# BACKPMAN21_PwrSw.net
KiCad netlist of a schematic drawn in Altium Designer
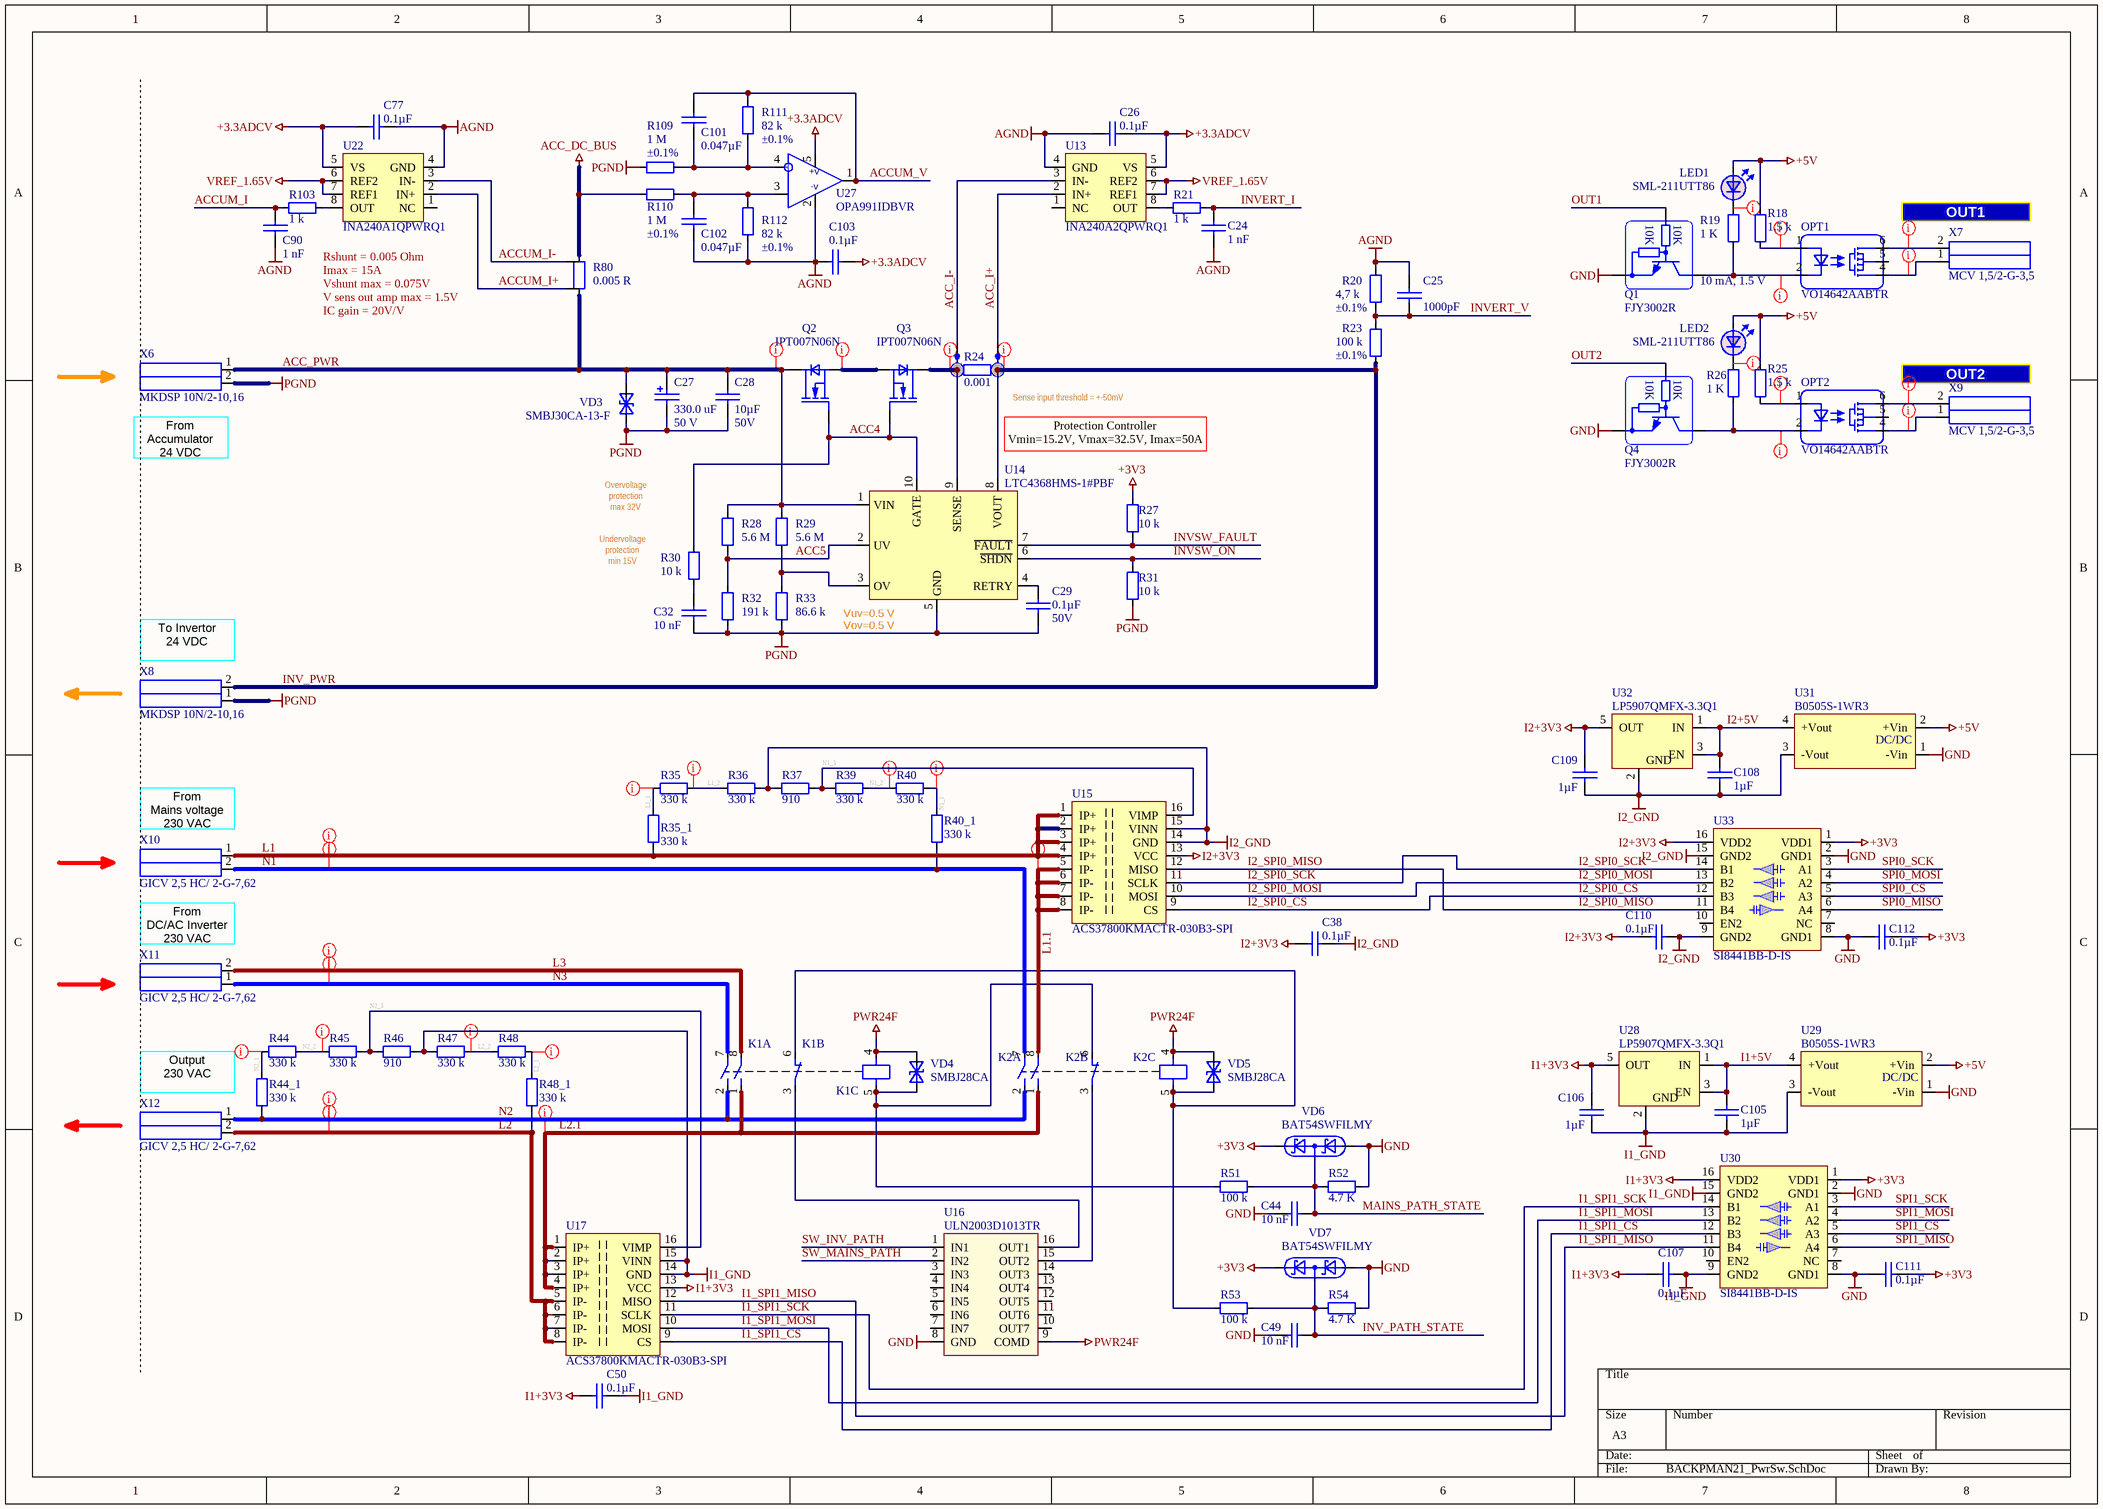
[diagram p0: BACKPMAN21_PwrSw.SchDoc]

(export (version "E")
  (design (tool "Eeschema 10.0.6"))
  (components
    (comp (ref "B1")
      (value "Net tie 0.3mm")
      (footprint "Net tee 0.3 mm")
      (libsource (lib "ea_Mechanical") (part "Net tie 0.3mm"))
    )
    (comp (ref "B2")
      (value "Net tie 0.3mm")
      (footprint "Net tee 0.3 mm")
      (libsource (lib "ea_Mechanical") (part "Net tie 0.3mm"))
    )
    (comp (ref "C24")
      (value "1 nF")
      (footprint "0603 CAP")
      (description "1000pF, ±5%, 50V, X7R, 0603 (1608 Metric), -55°C ~ 125°C, -, General Purpose")
      (fields (field (name "PART NUMBER") "CC0603JRX7R9BB102") (field (name "MANUFACTURER") "Yageo"))
      (libsource (lib "ea_PassivComps") (part "Capacitor"))
    )
    (comp (ref "C25")
      (value "1000pF")
      (footprint "0603 CAP")
      (description "1000pF, ±10%, 16V, X7R, 0603 (1608 Metric), -55°C ~ 125°C, -, General Purpose")
      (fields
        (field (name "PART NUMBER") "885012206034")
        (field (name "MANUFACTURER") "Wurth Electronics Inc.")
      )
      (libsource (lib "ea_PassivComps") (part "Capacitor"))
    )
    (comp (ref "C26")
      (value "0.1µF")
      (footprint "0603 CAP")
      (description "0.1µF, ±10%, 50V, X8L, 0603 (1608 Metric), -55°C ~ 150°C, -, Automotive")
      (fields
        (field (name "PART NUMBER") "GCM188L81H104KA57D")
        (field (name "MANUFACTURER") "Murata Electronics North America")
      )
      (libsource (lib "ea_PassivComps") (part "Capacitor"))
    )
    (comp (ref "C27")
      (value "330.0 uF")
      (footprint "UUD1V331MNL1GS")
      (description "330 uF, 50V, 120 mOhm @ 100kHz, 585 mA, 10x10, -50...+105 C")
      (fields
        (field (name "MANUFACTURER") "Panasonic Electronic Components")
        (field (name "VOLTAGE") "50 V")
        (field (name "TOLERANCE") "±20%")
      )
      (libsource (lib "ea_Capacitors") (part "EEE-FT1H331GP"))
    )
    (comp (ref "C28")
      (value "10µF")
      (footprint "1210 CAP")
      (description "10µF, ±10%, 50V, X7S, 1210 (3225 Metric), -55°C ~ 125°C, Low ESL, General Purpose")
      (fields
        (field (name "VOLTAGE - RATED") "50V")
        (field (name "PART NUMBER") "C3225X7S1H106K250AB")
        (field (name "MANUFACTURER") "TDK Corporation")
      )
      (libsource (lib "ea_PassivComps") (part "Capacitor"))
    )
    (comp (ref "C29")
      (value "0.1µF")
      (footprint "0603 CAP")
      (description "0.1µF, ±10%, 50V, X8L, 0603 (1608 Metric), -55°C ~ 150°C, -, Automotive")
      (fields
        (field (name "VOLTAGE - RATED") "50V")
        (field (name "PART NUMBER") "GCM188L81H104KA57D")
        (field (name "MANUFACTURER") "Murata Electronics North America")
      )
      (libsource (lib "ea_PassivComps") (part "Capacitor"))
    )
    (comp (ref "C32")
      (value "10 nF")
      (footprint "1608[0603]")
      (description "10 nF, 50V, 10%, X7R, 0603 SMD MLC Capacitor")
      (fields (field (name "TOLERANCE") "±10%") (field (name "MANUFACTURER") "Murata Electronics"))
      (libsource (lib "ea_Capacitors") (part "CVNF010K0603"))
    )
    (comp (ref "C38")
      (value "0.1µF")
      (footprint "0603 CAP")
      (description "0.1µF, ±10%, 16V, X7R, 0603 (1608 Metric), -55°C ~ 125°C, -, General Purpose")
      (fields
        (field (name "PART NUMBER") "CL10B104KO8NNNC")
        (field (name "MANUFACTURER") "Samsung Electro-Mechanics")
      )
      (libsource (lib "ea_PassivComps") (part "Capacitor"))
    )
    (comp (ref "C44")
      (value "10 nF")
      (footprint "1608[0603]")
      (description "10 nF, 50V, 10%, X7R, 0603 SMD MLC Capacitor")
      (fields (field (name "TOLERANCE") "±10%") (field (name "MANUFACTURER") "Murata Electronics"))
      (libsource (lib "ea_Capacitors") (part "CVNF010K0603"))
    )
    (comp (ref "C49")
      (value "10 nF")
      (footprint "1608[0603]")
      (description "10 nF, 50V, 10%, X7R, 0603 SMD MLC Capacitor")
      (fields (field (name "TOLERANCE") "±10%") (field (name "MANUFACTURER") "Murata Electronics"))
      (libsource (lib "ea_Capacitors") (part "CVNF010K0603"))
    )
    (comp (ref "C50")
      (value "0.1µF")
      (footprint "0603 CAP")
      (description "0.1µF, ±10%, 16V, X7R, 0603 (1608 Metric), -55°C ~ 125°C, -, General Purpose")
      (fields
        (field (name "PART NUMBER") "CL10B104KO8NNNC")
        (field (name "MANUFACTURER") "Samsung Electro-Mechanics")
      )
      (libsource (lib "ea_PassivComps") (part "Capacitor"))
    )
    (comp (ref "C77")
      (value "0.1µF")
      (footprint "0603 CAP")
      (description "0.1µF, ±10%, 50V, X8L, 0603 (1608 Metric), -55°C ~ 150°C, -, Automotive")
      (fields
        (field (name "PART NUMBER") "GCM188L81H104KA57D")
        (field (name "MANUFACTURER") "Murata Electronics North America")
      )
      (libsource (lib "ea_PassivComps") (part "Capacitor"))
    )
    (comp (ref "C90")
      (value "1 nF")
      (footprint "0603 CAP")
      (description "1000pF, ±5%, 50V, X7R, 0603 (1608 Metric), -55°C ~ 125°C, -, General Purpose")
      (fields (field (name "PART NUMBER") "CC0603JRX7R9BB102") (field (name "MANUFACTURER") "Yageo"))
      (libsource (lib "ea_PassivComps") (part "Capacitor"))
    )
    (comp (ref "C101")
      (value "0.047µF")
      (footprint "0603 CAP")
      (description "0.047µF, ±5%, 50V, X7R, 0603 (1608 Metric), -55°C ~ 125°C, -, General Purpose")
      (fields (field (name "PART NUMBER") "CC0603JRX7R9BB473") (field (name "MANUFACTURER") "Yageo"))
      (libsource (lib "ea_PassivComps") (part "Capacitor"))
    )
    (comp (ref "C102")
      (value "0.047µF")
      (footprint "0603 CAP")
      (description "0.047µF, ±5%, 50V, X7R, 0603 (1608 Metric), -55°C ~ 125°C, -, General Purpose")
      (fields (field (name "PART NUMBER") "CC0603JRX7R9BB473") (field (name "MANUFACTURER") "Yageo"))
      (libsource (lib "ea_PassivComps") (part "Capacitor"))
    )
    (comp (ref "C103")
      (value "0.1µF")
      (footprint "0603 CAP")
      (description "0.1µF, ±10%, 50V, X8L, 0603 (1608 Metric), -55°C ~ 150°C, -, Automotive")
      (fields
        (field (name "PART NUMBER") "GCM188L81H104KA57D")
        (field (name "MANUFACTURER") "Murata Electronics North America")
      )
      (libsource (lib "ea_PassivComps") (part "Capacitor"))
    )
    (comp (ref "C105")
      (value "1µF")
      (footprint "0603 CAP")
      (description "1µF, ±10%, 16V, X7R, 0603 (1608 Metric), -55°C ~ 125°C, -, General Purpose")
      (fields
        (field (name "PART NUMBER") "CL10B105KO8NNNC")
        (field (name "MANUFACTURER") "Samsung Electro-Mechanics")
      )
      (libsource (lib "ea_PassivComps") (part "Capacitor"))
    )
    (comp (ref "C106")
      (value "1µF")
      (footprint "0603 CAP")
      (description "1µF, ±10%, 16V, X7R, 0603 (1608 Metric), -55°C ~ 125°C, -, General Purpose")
      (fields
        (field (name "PART NUMBER") "CL10B105KO8NNNC")
        (field (name "MANUFACTURER") "Samsung Electro-Mechanics")
      )
      (libsource (lib "ea_PassivComps") (part "Capacitor"))
    )
    (comp (ref "C107")
      (value "0.1µF")
      (footprint "0603 CAP")
      (description "0.1µF, ±10%, 16V, X7R, 0603 (1608 Metric), -55°C ~ 125°C, -, General Purpose")
      (fields
        (field (name "PART NUMBER") "CL10B104KO8NNNC")
        (field (name "MANUFACTURER") "Samsung Electro-Mechanics")
      )
      (libsource (lib "ea_PassivComps") (part "Capacitor"))
    )
    (comp (ref "C108")
      (value "1µF")
      (footprint "0603 CAP")
      (description "1µF, ±10%, 16V, X7R, 0603 (1608 Metric), -55°C ~ 125°C, -, General Purpose")
      (fields
        (field (name "PART NUMBER") "CL10B105KO8NNNC")
        (field (name "MANUFACTURER") "Samsung Electro-Mechanics")
      )
      (libsource (lib "ea_PassivComps") (part "Capacitor"))
    )
    (comp (ref "C109")
      (value "1µF")
      (footprint "0603 CAP")
      (description "1µF, ±10%, 16V, X7R, 0603 (1608 Metric), -55°C ~ 125°C, -, General Purpose")
      (fields
        (field (name "PART NUMBER") "CL10B105KO8NNNC")
        (field (name "MANUFACTURER") "Samsung Electro-Mechanics")
      )
      (libsource (lib "ea_PassivComps") (part "Capacitor"))
    )
    (comp (ref "C110")
      (value "0.1µF")
      (footprint "0603 CAP")
      (description "0.1µF, ±10%, 16V, X7R, 0603 (1608 Metric), -55°C ~ 125°C, -, General Purpose")
      (fields
        (field (name "PART NUMBER") "CL10B104KO8NNNC")
        (field (name "MANUFACTURER") "Samsung Electro-Mechanics")
      )
      (libsource (lib "ea_PassivComps") (part "Capacitor"))
    )
    (comp (ref "C111")
      (value "0.1µF")
      (footprint "0603 CAP")
      (description "0.1µF, ±10%, 16V, X7R, 0603 (1608 Metric), -55°C ~ 125°C, -, General Purpose")
      (fields
        (field (name "PART NUMBER") "CL10B104KO8NNNC")
        (field (name "MANUFACTURER") "Samsung Electro-Mechanics")
      )
      (libsource (lib "ea_PassivComps") (part "Capacitor"))
    )
    (comp (ref "C112")
      (value "0.1µF")
      (footprint "0603 CAP")
      (description "0.1µF, ±10%, 16V, X7R, 0603 (1608 Metric), -55°C ~ 125°C, -, General Purpose")
      (fields
        (field (name "PART NUMBER") "CL10B104KO8NNNC")
        (field (name "MANUFACTURER") "Samsung Electro-Mechanics")
      )
      (libsource (lib "ea_PassivComps") (part "Capacitor"))
    )
    (comp (ref "K1")
      (value "AHES4292")
      (footprint "AHES4292")
      (fields (field (name "PARTNUM") "255-5914-ND") (field (name "MANUFACTURER") "Panasonic Electric Works"))
      (libsource (lib "ea_Relay") (part "AHES4292"))
    )
    (comp (ref "K2")
      (value "AHES4292")
      (footprint "AHES4292")
      (fields (field (name "PARTNUM") "255-5914-ND") (field (name "MANUFACTURER") "Panasonic Electric Works"))
      (libsource (lib "ea_Relay") (part "AHES4292"))
    )
    (comp (ref "LED1")
      (value "SML-211UTT86")
      (footprint "0805 LED")
      (description "0805 red LED, hibright, 2 mA, 1.8V, 130°")
      (fields (field (name "MANUFACTURER") "Rohm") (field (name "PARTNUM") "511-1292-1-ND"))
      (libsource (lib "ea_Indicators") (part "SML-211UTT86"))
    )
    (comp (ref "LED2")
      (value "SML-211UTT86")
      (footprint "0805 LED")
      (description "0805 red LED, hibright, 2 mA, 1.8V, 130°")
      (fields (field (name "MANUFACTURER") "Rohm") (field (name "PARTNUM") "511-1292-1-ND"))
      (libsource (lib "ea_Indicators") (part "SML-211UTT86"))
    )
    (comp (ref "OPT1")
      (value "VO14642AABTR")
      (footprint "DIP-6 SMD")
      (description "Opto relay, SPST-NO, AC DC, 250 mOhm, 2A, 0-60V, 6-SMD, -55..50C")
      (fields
        (field (name "MANUFACTURER") "Vishay Semiconductor Opto Division")
        (field (name "PARTNUM") "VO14642AABCT-ND")
      )
      (libsource (lib "ea_Opto") (part "VO14642AABTR"))
    )
    (comp (ref "OPT2")
      (value "VO14642AABTR")
      (footprint "DIP-6 SMD")
      (description "Opto relay, SPST-NO, AC DC, 250 mOhm, 2A, 0-60V, 6-SMD, -55..50C")
      (fields
        (field (name "MANUFACTURER") "Vishay Semiconductor Opto Division")
        (field (name "PARTNUM") "VO14642AABCT-ND")
      )
      (libsource (lib "ea_Opto") (part "VO14642AABTR"))
    )
    (comp (ref "Q1")
      (value "FJY3002R")
      (footprint "SOT-523F")
      (description "NPN 50V 100MA SOT-523F")
      (fields
        (field (name "MANUFACTURER") "Fairchild Semiconductor")
        (field (name "PARTNUM") "FJY3002RCT-ND")
      )
      (libsource (lib "ea_Transistors") (part "FJY3002R"))
    )
    (comp (ref "Q2")
      (value "IPT007N06N")
      (footprint "PG-HSOF-8-1 (8-PowerSFN) Infineon")
      (description "MOSFET N CH 60V 300A, 0.75 mOhm @ 150A 10V, 287nC @ 10V, PG-HSOF-8-1, -55°C ~ 175°C")
      (fields
        (field (name "MANUFACTURER") "Infineon Technologies")
        (field (name "PARTNUM") "IPT007N06NATMA1CT-ND")
      )
      (libsource (lib "ea_MOSFET_&_drivers") (part "IPT007N06NATMA1"))
    )
    (comp (ref "Q3")
      (value "IPT007N06N")
      (footprint "PG-HSOF-8-1 (8-PowerSFN) Infineon")
      (description "MOSFET N CH 60V 300A, 0.75 mOhm @ 150A 10V, 287nC @ 10V, PG-HSOF-8-1, -55°C ~ 175°C")
      (fields
        (field (name "MANUFACTURER") "Infineon Technologies")
        (field (name "PARTNUM") "IPT007N06NATMA1CT-ND")
      )
      (libsource (lib "ea_MOSFET_&_drivers") (part "IPT007N06NATMA1"))
    )
    (comp (ref "Q4")
      (value "FJY3002R")
      (footprint "SOT-523F")
      (description "NPN 50V 100MA SOT-523F")
      (fields
        (field (name "MANUFACTURER") "Fairchild Semiconductor")
        (field (name "PARTNUM") "FJY3002RCT-ND")
      )
      (libsource (lib "ea_Transistors") (part "FJY3002R"))
    )
    (comp (ref "R18")
      (value "1.5 k")
      (footprint "0603")
      (fields
        (field (name "MANUFACTURER") "Stackpole Electronics Inc.")
        (field (name "TOLERANCE") "±1%")
        (field (name "VOLTAGE") "75V")
      )
      (libsource (lib "") (part "Resistor_2"))
    )
    (comp (ref "R19")
      (value "1 K")
      (footprint "0603")
      (description "1 K, 1%, 0603, SMD Resistor, Taped")
      (fields (field (name "MANUFACTURER") "Vishay") (field (name "TOLERANCE") "1%"))
      (libsource (lib "ea_Resistors_0603") (part "RL0603K001-1"))
    )
    (comp (ref "R20")
      (value "4,7 k")
      (footprint "0603")
      (fields
        (field (name "MANUFACTURER") "Panasonic Electronic Components")
        (field (name "TOLERANCE") "±0.1%")
        (field (name "VOLTAGE") "75V")
        (field (name "PARTNUM") "P4.7KDBCT-ND")
      )
      (libsource (lib "") (part "Resistor_3"))
    )
    (comp (ref "R21")
      (value "1 k")
      (footprint "0603")
      (fields
        (field (name "MANUFACTURER") "Stackpole Electronics Inc.")
        (field (name "TOLERANCE") "±1%")
        (field (name "VOLTAGE") "75V")
      )
      (libsource (lib "ea_PassivComps") (part "Resistor"))
    )
    (comp (ref "R23")
      (value "100 k")
      (footprint "1206")
      (fields
        (field (name "MANUFACTURER") "Panasonic Electronic Components")
        (field (name "TOLERANCE") "±0.1%")
        (field (name "VOLTAGE") "200V")
        (field (name "PARTNUM") "ERA-8APB104V")
      )
      (libsource (lib "") (part "Resistor_2"))
    )
    (comp (ref "R24")
      (value "0.001")
      (footprint "WSR52L000FEA")
      (description "Curr.sens.res. 0.001 OHM 5W 1% 4527 SMD")
      (fields (field (name "MANUFACTURER") "Vishay/Dale") (field (name "TOLERANCE") "1%"))
      (libsource (lib "ea_Resistors") (part "WSR51L000FEA"))
    )
    (comp (ref "R25")
      (value "1.5 k")
      (footprint "0603")
      (fields
        (field (name "MANUFACTURER") "Stackpole Electronics Inc.")
        (field (name "TOLERANCE") "±1%")
        (field (name "VOLTAGE") "75V")
      )
      (libsource (lib "") (part "Resistor_2"))
    )
    (comp (ref "R26")
      (value "1 K")
      (footprint "0603")
      (description "1 K, 1%, 0603, SMD Resistor, Taped")
      (fields (field (name "MANUFACTURER") "Vishay") (field (name "TOLERANCE") "1%"))
      (libsource (lib "ea_Resistors_0603") (part "RL0603K001-1"))
    )
    (comp (ref "R27")
      (value "10 k")
      (footprint "0603")
      (fields
        (field (name "MANUFACTURER") "Bourns Inc.")
        (field (name "TOLERANCE") "±1%")
        (field (name "VOLTAGE") "75V")
      )
      (libsource (lib "") (part "Resistor_1"))
    )
    (comp (ref "R28")
      (value "5.6 M")
      (footprint "0805")
      (fields
        (field (name "MANUFACTURER") "Vishay Dale")
        (field (name "TOLERANCE") "±1%")
        (field (name "VOLTAGE") "150V")
      )
      (libsource (lib "") (part "Resistor_1"))
    )
    (comp (ref "R29")
      (value "5.6 M")
      (footprint "0805")
      (fields
        (field (name "MANUFACTURER") "Vishay Dale")
        (field (name "TOLERANCE") "±1%")
        (field (name "VOLTAGE") "150V")
      )
      (libsource (lib "") (part "Resistor_1"))
    )
    (comp (ref "R30")
      (value "10 k")
      (footprint "0603")
      (fields
        (field (name "MANUFACTURER") "Bourns Inc.")
        (field (name "TOLERANCE") "±1%")
        (field (name "VOLTAGE") "75V")
      )
      (libsource (lib "") (part "Resistor_3"))
    )
    (comp (ref "R31")
      (value "10 k")
      (footprint "0603")
      (fields
        (field (name "MANUFACTURER") "Bourns Inc.")
        (field (name "TOLERANCE") "±1%")
        (field (name "VOLTAGE") "75V")
      )
      (libsource (lib "") (part "Resistor_1"))
    )
    (comp (ref "R32")
      (value "191 k")
      (footprint "0603")
      (fields
        (field (name "MANUFACTURER") "Stackpole Electronics Inc.")
        (field (name "TOLERANCE") "±1%")
        (field (name "VOLTAGE") "75V")
      )
      (libsource (lib "") (part "Resistor_1"))
    )
    (comp (ref "R33")
      (value "86.6 k")
      (footprint "0603")
      (fields
        (field (name "MANUFACTURER") "Stackpole Electronics Inc.")
        (field (name "TOLERANCE") "±1%")
        (field (name "VOLTAGE") "75V")
      )
      (libsource (lib "") (part "Resistor_1"))
    )
    (comp (ref "R35")
      (value "330 k")
      (footprint "1206")
      (fields
        (field (name "MANUFACTURER") "Stackpole Electronics Inc.")
        (field (name "TOLERANCE") "±1%")
        (field (name "VOLTAGE") "200V")
      )
      (libsource (lib "ea_PassivComps") (part "Resistor"))
    )
    (comp (ref "R35_1")
      (value "330 k")
      (footprint "1206")
      (fields
        (field (name "MANUFACTURER") "Stackpole Electronics Inc.")
        (field (name "TOLERANCE") "±1%")
        (field (name "VOLTAGE") "200V")
      )
      (libsource (lib "") (part "Resistor_1"))
    )
    (comp (ref "R36")
      (value "330 k")
      (footprint "1206")
      (fields
        (field (name "MANUFACTURER") "Stackpole Electronics Inc.")
        (field (name "TOLERANCE") "±1%")
        (field (name "VOLTAGE") "200V")
      )
      (libsource (lib "ea_PassivComps") (part "Resistor"))
    )
    (comp (ref "R37")
      (value "910")
      (footprint "0603")
      (fields
        (field (name "MANUFACTURER") "Stackpole Electronics Inc.")
        (field (name "TOLERANCE") "±1%")
        (field (name "VOLTAGE") "75V")
      )
      (libsource (lib "ea_PassivComps") (part "Resistor"))
    )
    (comp (ref "R39")
      (value "330 k")
      (footprint "1206")
      (fields
        (field (name "MANUFACTURER") "Stackpole Electronics Inc.")
        (field (name "TOLERANCE") "±1%")
        (field (name "VOLTAGE") "200V")
      )
      (libsource (lib "ea_PassivComps") (part "Resistor"))
    )
    (comp (ref "R40")
      (value "330 k")
      (footprint "1206")
      (fields
        (field (name "MANUFACTURER") "Stackpole Electronics Inc.")
        (field (name "TOLERANCE") "±1%")
        (field (name "VOLTAGE") "200V")
      )
      (libsource (lib "ea_PassivComps") (part "Resistor"))
    )
    (comp (ref "R40_1")
      (value "330 k")
      (footprint "1206")
      (fields
        (field (name "MANUFACTURER") "Stackpole Electronics Inc.")
        (field (name "TOLERANCE") "±1%")
        (field (name "VOLTAGE") "200V")
      )
      (libsource (lib "") (part "Resistor_1"))
    )
    (comp (ref "R44")
      (value "330 k")
      (footprint "1206")
      (fields
        (field (name "MANUFACTURER") "Stackpole Electronics Inc.")
        (field (name "TOLERANCE") "±1%")
        (field (name "VOLTAGE") "200V")
      )
      (libsource (lib "ea_PassivComps") (part "Resistor"))
    )
    (comp (ref "R44_1")
      (value "330 k")
      (footprint "1206")
      (fields
        (field (name "MANUFACTURER") "Stackpole Electronics Inc.")
        (field (name "TOLERANCE") "±1%")
        (field (name "VOLTAGE") "200V")
      )
      (libsource (lib "") (part "Resistor_1"))
    )
    (comp (ref "R45")
      (value "330 k")
      (footprint "1206")
      (fields
        (field (name "MANUFACTURER") "Stackpole Electronics Inc.")
        (field (name "TOLERANCE") "±1%")
        (field (name "VOLTAGE") "200V")
      )
      (libsource (lib "ea_PassivComps") (part "Resistor"))
    )
    (comp (ref "R46")
      (value "910")
      (footprint "0603")
      (fields
        (field (name "MANUFACTURER") "Stackpole Electronics Inc.")
        (field (name "TOLERANCE") "±1%")
        (field (name "VOLTAGE") "75V")
      )
      (libsource (lib "ea_PassivComps") (part "Resistor"))
    )
    (comp (ref "R47")
      (value "330 k")
      (footprint "1206")
      (fields
        (field (name "MANUFACTURER") "Stackpole Electronics Inc.")
        (field (name "TOLERANCE") "±1%")
        (field (name "VOLTAGE") "200V")
      )
      (libsource (lib "ea_PassivComps") (part "Resistor"))
    )
    (comp (ref "R48")
      (value "330 k")
      (footprint "1206")
      (fields
        (field (name "MANUFACTURER") "Stackpole Electronics Inc.")
        (field (name "TOLERANCE") "±1%")
        (field (name "VOLTAGE") "200V")
      )
      (libsource (lib "ea_PassivComps") (part "Resistor"))
    )
    (comp (ref "R48_1")
      (value "330 k")
      (footprint "1206")
      (fields
        (field (name "MANUFACTURER") "Stackpole Electronics Inc.")
        (field (name "TOLERANCE") "±1%")
        (field (name "VOLTAGE") "200V")
      )
      (libsource (lib "") (part "Resistor_1"))
    )
    (comp (ref "R51")
      (value "100 k")
      (footprint "1206")
      (fields
        (field (name "MANUFACTURER") "Stackpole Electronics Inc.")
        (field (name "TOLERANCE") "±1%")
        (field (name "VOLTAGE") "200V")
      )
      (libsource (lib "ea_PassivComps") (part "Resistor"))
    )
    (comp (ref "R52")
      (value "4.7 K")
      (footprint "0603")
      (description "4.7 K, 1%, 0603, SMD Resistor, Taped")
      (fields (field (name "MANUFACTURER") "Vishay Dale") (field (name "TOLERANCE") "1%"))
      (libsource (lib "ea_Resistors") (part "RL0603K004.7-1"))
    )
    (comp (ref "R53")
      (value "100 k")
      (footprint "1206")
      (fields
        (field (name "MANUFACTURER") "Stackpole Electronics Inc.")
        (field (name "TOLERANCE") "±1%")
        (field (name "VOLTAGE") "200V")
      )
      (libsource (lib "ea_PassivComps") (part "Resistor"))
    )
    (comp (ref "R54")
      (value "4.7 K")
      (footprint "0603")
      (description "4.7 K, 1%, 0603, SMD Resistor, Taped")
      (fields (field (name "MANUFACTURER") "Vishay Dale") (field (name "TOLERANCE") "1%"))
      (libsource (lib "ea_Resistors") (part "RL0603K004.7-1"))
    )
    (comp (ref "R80")
      (value "0.005 R")
      (footprint "FC4L110")
      (description "Curr.sens.res. 0.005 OHM 5W 1% , 4320 (50110 Metric)")
      (fields (field (name "MANUFACTURER") "Ohmite") (field (name "TOLERANCE") "1%"))
      (libsource (lib "ea_Resistors") (part "FC4L110R005FER"))
    )
    (comp (ref "R103")
      (value "1 k")
      (footprint "0603")
      (fields
        (field (name "MANUFACTURER") "Stackpole Electronics Inc.")
        (field (name "TOLERANCE") "±1%")
        (field (name "VOLTAGE") "75V")
      )
      (libsource (lib "") (part "Resistor_3"))
    )
    (comp (ref "R109")
      (value "1 M")
      (footprint "0603")
      (description "1 MOhms, ±0.1%, 0.1W, 1/10W, Thin Film, ±25ppm/°C, 0603 (1608 Metric), -55°C ~ 155°C, -")
      (fields
        (field (name "MANUFACTURER") "Yageo")
        (field (name "TOLERANCE") "±0.1%")
        (field (name "VOLTAGE") "75V")
      )
      (libsource (lib "ea_PassivComps") (part "Resistor"))
    )
    (comp (ref "R110")
      (value "1 M")
      (footprint "0603")
      (description "1 MOhms, ±0.1%, 0.1W, 1/10W, Thin Film, ±25ppm/°C, 0603 (1608 Metric), -55°C ~ 155°C, -")
      (fields
        (field (name "MANUFACTURER") "Yageo")
        (field (name "TOLERANCE") "±0.1%")
        (field (name "VOLTAGE") "75V")
      )
      (libsource (lib "ea_PassivComps") (part "Resistor"))
    )
    (comp (ref "R111")
      (value "82 k")
      (footprint "0603")
      (fields
        (field (name "MANUFACTURER") "Panasonic Electronic Components")
        (field (name "TOLERANCE") "±0.1%")
        (field (name "VOLTAGE") "75V")
        (field (name "PARTNUM") "P82KDBCT-ND")
      )
      (libsource (lib "") (part "Resistor_1"))
    )
    (comp (ref "R112")
      (value "82 k")
      (footprint "0603")
      (fields
        (field (name "MANUFACTURER") "Panasonic Electronic Components")
        (field (name "TOLERANCE") "±0.1%")
        (field (name "VOLTAGE") "75V")
        (field (name "PARTNUM") "P82KDBCT-ND")
      )
      (libsource (lib "") (part "Resistor_1"))
    )
    (comp (ref "U13")
      (value "INA240A2QPWRQ1")
      (footprint "TI TSSOP-8")
      (description "Current Sense Amplifier, 50V/V, 2V/us, 400KHz, -40°C ~ 125°C, 8-TSSOP")
      (fields (field (name "MANUFACTURER") "Texas Instruments") (field (name "PARTNUM") "296-50473-1-ND"))
      (libsource (lib "ea_IC_OPAmps_AnComparators") (part "INA240A2QPWRQ1"))
    )
    (comp (ref "U14")
      (value "LTC4368HMS-1#PBF")
      (footprint "10-Lead Plastic MSOP Linear")
      (fields (field (name "MANUFACTURER") "Analog Devices") (field (name "PARTNUM") "LTC4368HMS-1#PBF-ND"))
      (libsource (lib "ea_IC_drivers") (part "LTC4368HMS-1_PBF"))
    )
    (comp (ref "U15")
      (value "ACS37800KMACTR-030B3-SPI")
      (footprint "16-Pin SOICW")
      (fields
        (field (name "MANUFACTURER") "Allegro MicroSystems")
        (field (name "PARTNUM") "620-ACS37800KMACTR-030B3-SPICT-ND")
      )
      (libsource (lib "ea_IC_sensors") (part "ACS37800KMACTR-030B3-SPI"))
    )
    (comp (ref "U16")
      (value "ULN2003D1013TR")
      (footprint "SO-16")
      (description "TRANS 7 NPN DARL 50V 500MA 16SO")
      (fields (field (name "MANUFACTURER") "STMicroelectronics") (field (name "PARTNUM") "497-2345-1-ND"))
      (libsource (lib "ea_IC_registers_buffers") (part "ULN2003D1013TR"))
    )
    (comp (ref "U17")
      (value "ACS37800KMACTR-030B3-SPI")
      (footprint "16-Pin SOICW")
      (fields
        (field (name "MANUFACTURER") "Allegro MicroSystems")
        (field (name "PARTNUM") "620-ACS37800KMACTR-030B3-SPICT-ND")
      )
      (libsource (lib "ea_IC_sensors") (part "ACS37800KMACTR-030B3-SPI"))
    )
    (comp (ref "U22")
      (value "INA240A1QPWRQ1")
      (footprint "TI TSSOP-8")
      (description "Current Sense Amplifier, 20V/V, 2V/us, 400KHz, -40°C ~ 125°C, 8-TSSOP")
      (fields (field (name "MANUFACTURER") "Texas Instruments") (field (name "PARTNUM") "296-50472-1-ND"))
      (libsource (lib "ea_IC_OPAmps_AnComparators") (part "INA240A1QPWRQ1"))
    )
    (comp (ref "U27")
      (value "OPA991IDBVR")
      (footprint "SOT23-5")
      (description "OpAmp,  Rail-to-Rail,  4,5MHz, VSS 2.7V ~ 40V, Vofs125µV,  SOT-23-5, -40°C ~ 125°C")
      (fields
        (field (name "MANUFACTURER") "Texas Instruments")
        (field (name "PARTNUM") "296-OPA991IDBVRCT-ND")
      )
      (libsource (lib "ea_IC_OPAmps_AnComparators") (part "OPA991IDBVR"))
    )
    (comp (ref "U28")
      (value "LP5907QMFX-3.3Q1")
      (footprint "SOT23-5")
      (description "LDO 3.3 V, 250 mA, Vin < 5.5V, Iq < 12uA, -40..+125 C, SOT23-5")
      (fields (field (name "MANUFACTURER") "Texas Instruments") (field (name "PARTNUM") "296-40365-1-ND"))
      (libsource (lib "ea_IC_Power_Reg_Ref_Sw") (part "LP5907QMFX-3.3Q1"))
    )
    (comp (ref "U29")
      (value "B0505S-1WR3")
      (footprint "Recom 4-SIP module")
      (description "200mA, DC-DC Unregulated Single Output , 5V in, 5 V out,  -40°C ~ 105°C")
      (fields
        (field (name "MANUFACTURER") "Mornsun America, LLC")
        (field (name "PARTNUM") "2725-B0505S-1WR3-ND")
      )
      (libsource (lib "ea_PowerSources") (part "B0505S-1WR3"))
    )
    (comp (ref "U30")
      (value "SI8441BB-D-IS")
      (footprint "SO-G16/D10.4")
      (description "IC ISOLATOR 4CH 5.5V 16-SOIC")
      (fields
        (field (name "MANUFACTURER") "Silicon Laboratories Inc")
        (field (name "PARTNUM") "336-1762-5-ND")
      )
      (libsource (lib "ea_IC_Isolated_Interfaces") (part "SI8441BB-D-IS"))
    )
    (comp (ref "U31")
      (value "B0505S-1WR3")
      (footprint "Recom 4-SIP module")
      (description "200mA, DC-DC Unregulated Single Output , 5V in, 5 V out,  -40°C ~ 105°C")
      (fields
        (field (name "MANUFACTURER") "Mornsun America, LLC")
        (field (name "PARTNUM") "2725-B0505S-1WR3-ND")
      )
      (libsource (lib "ea_PowerSources") (part "B0505S-1WR3"))
    )
    (comp (ref "U32")
      (value "LP5907QMFX-3.3Q1")
      (footprint "SOT23-5")
      (description "LDO 3.3 V, 250 mA, Vin < 5.5V, Iq < 12uA, -40..+125 C, SOT23-5")
      (fields (field (name "MANUFACTURER") "Texas Instruments") (field (name "PARTNUM") "296-40365-1-ND"))
      (libsource (lib "ea_IC_Power_Reg_Ref_Sw") (part "LP5907QMFX-3.3Q1"))
    )
    (comp (ref "U33")
      (value "SI8441BB-D-IS")
      (footprint "SO-G16/D10.4")
      (description "IC ISOLATOR 4CH 5.5V 16-SOIC")
      (fields
        (field (name "MANUFACTURER") "Silicon Laboratories Inc")
        (field (name "PARTNUM") "336-1762-5-ND")
      )
      (libsource (lib "ea_IC_Isolated_Interfaces") (part "SI8441BB-D-IS"))
    )
    (comp (ref "VD3")
      (value "SMBJ30CA-13-F")
      (footprint "DO-214AA_SMBJ BI")
      (description "TVS 600W, Vbr=33.3V, Vcl=48.4V,  Bidirectional, SMB, -55°C ~ 150°C")
      (fields
        (field (name "MANUFACTURER") "Diodes Incorporated")
        (field (name "PARTNUM") "SMBJ30CA-FDICT-ND")
      )
      (libsource (lib "ea_TVS_protection") (part "SMBJ30CA-13-F"))
    )
    (comp (ref "VD4")
      (value "SMBJ28CA")
      (footprint "DO-214AA_SMBJ")
      (description "TVS 600W 28V Bidirectional")
      (fields (field (name "MANUFACTURER") "Littelfuse") (field (name "PARTNUM") "SMBJ28CABCT-ND"))
      (libsource (lib "ea_TVS_protection") (part "SMBJ28CA"))
    )
    (comp (ref "VD5")
      (value "SMBJ28CA")
      (footprint "DO-214AA_SMBJ")
      (description "TVS 600W 28V Bidirectional")
      (fields (field (name "MANUFACTURER") "Littelfuse") (field (name "PARTNUM") "SMBJ28CABCT-ND"))
      (libsource (lib "ea_TVS_protection") (part "SMBJ28CA"))
    )
    (comp (ref "VD6")
      (value "BAT54SWFILMY")
      (footprint "SOT323-3")
      (description "Series Shottky Diodes array, 40V, 300 mA, SOT-323, -40°C...150°C")
      (fields (field (name "MANUFACTURER") "STMicroelectronics") (field (name "PARTNUM") "497-17757-1-ND"))
      (libsource (lib "ea_Diodes") (part "BAT54SWFILMY"))
    )
    (comp (ref "VD7")
      (value "BAT54SWFILMY")
      (footprint "SOT323-3")
      (description "Series Shottky Diodes array, 40V, 300 mA, SOT-323, -40°C...150°C")
      (fields (field (name "MANUFACTURER") "STMicroelectronics") (field (name "PARTNUM") "497-17757-1-ND"))
      (libsource (lib "ea_Diodes") (part "BAT54SWFILMY"))
    )
    (comp (ref "X6")
      (value "MKDSP 10N/2-10,16")
      (footprint "MKDSP 10N/ 2-10,16")
      (description "TERMINAL BLOCK, PCB, 10.16MM, 2WAY")
      (fields (field (name "MANUFACTURER") "PHOENIX CONTACT") (field (name "PARTNUM") "1734796"))
      (libsource (lib "ea_PhoenixContacts") (part "MKDSP 10N/2-10,16"))
    )
    (comp (ref "X7")
      (value "MCV 1,5/2-G-3,5")
      (footprint "mcv1.5-2-g_3.5 Green  + MC 1,5 2-ST-3,5 - 1840366")
      (description "HEADER, VERTICAL, 3.5MM, 2WAY")
      (fields (field (name "MANUFACTURER") "PHOENIX CONTACT") (field (name "PARTNUM") "1843606"))
      (libsource (lib "ea_PhoenixContacts") (part "MCV 1,5/2-G-3,5"))
    )
    (comp (ref "X8")
      (value "MKDSP 10N/2-10,16")
      (footprint "MKDSP 10N/ 2-10,16")
      (description "TERMINAL BLOCK, PCB, 10.16MM, 2WAY")
      (fields (field (name "MANUFACTURER") "PHOENIX CONTACT") (field (name "PARTNUM") "1734796"))
      (libsource (lib "ea_PhoenixContacts") (part "MKDSP 10N/2-10,16"))
    )
    (comp (ref "X9")
      (value "MCV 1,5/2-G-3,5")
      (footprint "mcv1.5-2-g_3.5 Green  + MC 1,5 2-ST-3,5 - 1840366")
      (description "HEADER, VERTICAL, 3.5MM, 2WAY")
      (fields (field (name "MANUFACTURER") "PHOENIX CONTACT") (field (name "PARTNUM") "1843606"))
      (libsource (lib "ea_PhoenixContacts") (part "MCV 1,5/2-G-3,5"))
    )
    (comp (ref "X10")
      (value "GICV 2,5 HC/ 2-G-7,62")
      (footprint "1756485 GICV 2,5 HC/2 -G-7,62")
      (fields (field (name "MANUFACTURER") "PHOENIX CONTACT") (field (name "PARTNUM") "1756485"))
      (libsource (lib "ea_Connectors_Power") (part "GICV 2,5 HC/ 2-G-7,62"))
    )
    (comp (ref "X11")
      (value "GICV 2,5 HC/ 2-G-7,62")
      (footprint "1756485 GICV 2,5 HC/2 -G-7,62")
      (fields (field (name "MANUFACTURER") "PHOENIX CONTACT") (field (name "PARTNUM") "1756485"))
      (libsource (lib "ea_Connectors_Power") (part "GICV 2,5 HC/ 2-G-7,62"))
    )
    (comp (ref "X12")
      (value "GICV 2,5 HC/ 2-G-7,62")
      (footprint "1756485 GICV 2,5 HC/2 -G-7,62")
      (fields (field (name "MANUFACTURER") "PHOENIX CONTACT") (field (name "PARTNUM") "1756485"))
      (libsource (lib "ea_Connectors_Power") (part "GICV 2,5 HC/ 2-G-7,62"))
    )
  )
  (nets
    (net (code "1") (name "+3.3ADCV") (class "Default")
      (node (ref "C103") (pin "1") (pinfunction "1_1") (pintype "passive"))
      (node (ref "C26") (pin "1") (pinfunction "1_1") (pintype "passive"))
      (node (ref "C77") (pin "1") (pinfunction "1_1") (pintype "passive"))
      (node (ref "U13") (pin "5") (pinfunction "VS_5") (pintype "passive"))
      (node (ref "U22") (pin "5") (pinfunction "VS_5") (pintype "passive"))
      (node (ref "U27") (pin "5") (pinfunction "V+_5") (pintype "power_in"))
    )
    (net (code "2") (name "+3V3") (class "Default")
      (node (ref "C111") (pin "2") (pinfunction "2_2") (pintype "passive"))
      (node (ref "C112") (pin "2") (pinfunction "2_2") (pintype "passive"))
      (node (ref "R27") (pin "2") (pinfunction "2_2") (pintype "passive"))
      (node (ref "U30") (pin "1") (pinfunction "VDD1_1") (pintype "passive"))
      (node (ref "U33") (pin "1") (pinfunction "VDD1_1") (pintype "passive"))
      (node (ref "VD6") (pin "2") (pinfunction "2_2") (pintype "passive"))
      (node (ref "VD7") (pin "2") (pinfunction "2_2") (pintype "passive"))
    )
    (net (code "3") (name "+5V") (class "Default")
      (node (ref "LED1") (pin "1") (pinfunction "1_1") (pintype "passive"))
      (node (ref "LED2") (pin "1") (pinfunction "1_1") (pintype "passive"))
      (node (ref "R18") (pin "1") (pinfunction "1_1") (pintype "passive"))
      (node (ref "R25") (pin "1") (pinfunction "1_1") (pintype "passive"))
      (node (ref "U29") (pin "2") (pinfunction "+Vin_2") (pintype "passive"))
      (node (ref "U31") (pin "2") (pinfunction "+Vin_2") (pintype "passive"))
    )
    (net (code "4") (name "/ACC4") (class "Default")
      (node (ref "Q2") (pin "1") (pinfunction "G_1") (pintype "passive"))
      (node (ref "Q3") (pin "1") (pinfunction "G_1") (pintype "passive"))
      (node (ref "R30") (pin "1") (pinfunction "1_1") (pintype "passive"))
      (node (ref "U14") (pin "10") (pinfunction "GATE_10") (pintype "passive"))
    )
    (net (code "5") (name "/ACC5") (class "Default")
      (node (ref "R28") (pin "1") (pinfunction "1_1") (pintype "passive"))
      (node (ref "R32") (pin "2") (pinfunction "2_2") (pintype "passive"))
      (node (ref "U14") (pin "2") (pinfunction "UV_2") (pintype "passive"))
    )
    (net (code "6") (name "/ACCUM_I") (class "Default")
      (node (ref "C90") (pin "2") (pinfunction "2_2") (pintype "passive"))
      (node (ref "R103") (pin "2") (pinfunction "2_2") (pintype "passive"))
    )
    (net (code "7") (name "/ACCUM_I+") (class "Default")
      (node (ref "R80") (pin "3") (pinfunction "1_3") (pintype "passive"))
      (node (ref "U22") (pin "2") (pinfunction "IN+_2") (pintype "passive"))
    )
    (net (code "8") (name "/ACCUM_I-") (class "Default")
      (node (ref "R80") (pin "4") (pinfunction "1_4") (pintype "passive"))
      (node (ref "U22") (pin "3") (pinfunction "IN-_3") (pintype "passive"))
    )
    (net (code "9") (name "/ACCUM_V") (class "Default")
      (node (ref "C101") (pin "1") (pinfunction "1_1") (pintype "passive"))
      (node (ref "R111") (pin "2") (pinfunction "2_2") (pintype "passive"))
      (node (ref "U27") (pin "1") (pinfunction "OUT_1") (pintype "passive"))
    )
    (net (code "10") (name "/ACC_I+") (class "Default")
      (node (ref "B2") (pin "2") (pinfunction "2_2") (pintype "passive"))
      (node (ref "U13") (pin "2") (pinfunction "IN+_2") (pintype "passive"))
    )
    (net (code "11") (name "/ACC_I-") (class "Default")
      (node (ref "B1") (pin "2") (pinfunction "2_2") (pintype "passive"))
      (node (ref "U13") (pin "3") (pinfunction "IN-_3") (pintype "passive"))
    )
    (net (code "12") (name "/ACC_PWR") (class "Default")
      (node (ref "C27") (pin "1") (pinfunction "1_1") (pintype "passive"))
      (node (ref "C28") (pin "1") (pinfunction "1_1") (pintype "passive"))
      (node (ref "Q2") (pin "3") (pinfunction "D_3") (pintype "passive"))
      (node (ref "R28") (pin "2") (pinfunction "2_2") (pintype "passive"))
      (node (ref "R29") (pin "2") (pinfunction "2_2") (pintype "passive"))
      (node (ref "R80") (pin "1") (pinfunction "1_1") (pintype "passive"))
      (node (ref "U14") (pin "1") (pinfunction "VIN_1") (pintype "passive"))
      (node (ref "VD3") (pin "2") (pinfunction "A_2") (pintype "passive"))
      (node (ref "X6") (pin "1") (pinfunction "1_1") (pintype "passive"))
    )
    (net (code "13") (name "/I1+5V") (class "Default")
      (node (ref "C105") (pin "1") (pinfunction "1_1") (pintype "passive"))
      (node (ref "U28") (pin "1") (pinfunction "IN_1") (pintype "power_in"))
      (node (ref "U28") (pin "3") (pinfunction "EN_3") (pintype "power_in"))
      (node (ref "U29") (pin "4") (pinfunction "+Vout_4") (pintype "passive"))
    )
    (net (code "14") (name "/I1_SPI1_CS") (class "Default")
      (node (ref "U17") (pin "9") (pinfunction "CS_9") (pintype "passive"))
      (node (ref "U30") (pin "12") (pinfunction "B3_12") (pintype "passive"))
    )
    (net (code "15") (name "/I1_SPI1_MISO") (class "Default")
      (node (ref "U17") (pin "12") (pinfunction "MISO_12") (pintype "passive"))
      (node (ref "U30") (pin "11") (pinfunction "B4_11") (pintype "passive"))
    )
    (net (code "16") (name "/I1_SPI1_MOSI") (class "Default")
      (node (ref "U17") (pin "10") (pinfunction "MOSI_10") (pintype "passive"))
      (node (ref "U30") (pin "13") (pinfunction "B2_13") (pintype "passive"))
    )
    (net (code "17") (name "/I1_SPI1_SCK") (class "Default")
      (node (ref "U17") (pin "11") (pinfunction "SCLK_11") (pintype "passive"))
      (node (ref "U30") (pin "14") (pinfunction "B1_14") (pintype "passive"))
    )
    (net (code "18") (name "/I2+5V") (class "Default")
      (node (ref "C108") (pin "1") (pinfunction "1_1") (pintype "passive"))
      (node (ref "U31") (pin "4") (pinfunction "+Vout_4") (pintype "passive"))
      (node (ref "U32") (pin "1") (pinfunction "IN_1") (pintype "power_in"))
      (node (ref "U32") (pin "3") (pinfunction "EN_3") (pintype "power_in"))
    )
    (net (code "19") (name "/I2_SPI0_CS") (class "Default")
      (node (ref "U15") (pin "9") (pinfunction "CS_9") (pintype "passive"))
      (node (ref "U33") (pin "12") (pinfunction "B3_12") (pintype "passive"))
    )
    (net (code "20") (name "/I2_SPI0_MISO") (class "Default")
      (node (ref "U15") (pin "12") (pinfunction "MISO_12") (pintype "passive"))
      (node (ref "U33") (pin "11") (pinfunction "B4_11") (pintype "passive"))
    )
    (net (code "21") (name "/I2_SPI0_MOSI") (class "Default")
      (node (ref "U15") (pin "10") (pinfunction "MOSI_10") (pintype "passive"))
      (node (ref "U33") (pin "13") (pinfunction "B2_13") (pintype "passive"))
    )
    (net (code "22") (name "/I2_SPI0_SCK") (class "Default")
      (node (ref "U15") (pin "11") (pinfunction "SCLK_11") (pintype "passive"))
      (node (ref "U33") (pin "14") (pinfunction "B1_14") (pintype "passive"))
    )
    (net (code "23") (name "/INVERT_I") (class "Default")
      (node (ref "C24") (pin "2") (pinfunction "2_2") (pintype "passive"))
      (node (ref "R21") (pin "2") (pinfunction "2_2") (pintype "passive"))
    )
    (net (code "24") (name "/INVERT_V") (class "Default")
      (node (ref "C25") (pin "2") (pinfunction "2_2") (pintype "passive"))
      (node (ref "R20") (pin "2") (pinfunction "2_2") (pintype "passive"))
      (node (ref "R23") (pin "1") (pinfunction "1_1") (pintype "passive"))
    )
    (net (code "25") (name "/INVSW_FAULT") (class "Default")
      (node (ref "R27") (pin "1") (pinfunction "1_1") (pintype "passive"))
      (node (ref "U14") (pin "7") (pinfunction "~{FAULT}_7") (pintype "passive"))
    )
    (net (code "26") (name "/INVSW_ON") (class "Default")
      (node (ref "R31") (pin "2") (pinfunction "2_2") (pintype "passive"))
      (node (ref "U14") (pin "6") (pinfunction "~{SHDN}_6") (pintype "passive"))
    )
    (net (code "27") (name "/INV_PATH_STATE") (class "Default")
      (node (ref "C49") (pin "1") (pinfunction "1_1") (pintype "passive"))
      (node (ref "R53") (pin "2") (pinfunction "2_2") (pintype "passive"))
      (node (ref "R54") (pin "2") (pinfunction "2_2") (pintype "passive"))
      (node (ref "VD7") (pin "3") (pinfunction "3_3") (pintype "passive"))
    )
    (net (code "28") (name "/INV_PWR") (class "Default")
      (node (ref "B2") (pin "1") (pinfunction "1_1") (pintype "passive"))
      (node (ref "R23") (pin "2") (pinfunction "2_2") (pintype "passive"))
      (node (ref "R24") (pin "1") (pinfunction "1_1") (pintype "passive"))
      (node (ref "U14") (pin "8") (pinfunction "VOUT_8") (pintype "passive"))
      (node (ref "X8") (pin "2") (pinfunction "2_2") (pintype "passive"))
    )
    (net (code "29") (name "/L1") (class "Default")
      (node (ref "R35_1") (pin "1") (pinfunction "1_1") (pintype "passive"))
      (node (ref "U15") (pin "1") (pinfunction "IP+_1") (pintype "passive"))
      (node (ref "U15") (pin "2") (pinfunction "IP+_2") (pintype "passive"))
      (node (ref "U15") (pin "3") (pinfunction "IP+_3") (pintype "passive"))
      (node (ref "U15") (pin "4") (pinfunction "IP+_4") (pintype "passive"))
      (node (ref "X10") (pin "1") (pinfunction "1_1") (pintype "passive"))
    )
    (net (code "30") (name "/L1.1") (class "Default")
      (node (ref "K2") (pin "8") (pinfunction "8_8") (pintype "passive"))
      (node (ref "U15") (pin "5") (pinfunction "IP-_5") (pintype "passive"))
      (node (ref "U15") (pin "6") (pinfunction "IP-_6") (pintype "passive"))
      (node (ref "U15") (pin "7") (pinfunction "IP-_7") (pintype "passive"))
      (node (ref "U15") (pin "8") (pinfunction "IP-_8") (pintype "passive"))
    )
    (net (code "31") (name "/L1_1") (class "Default")
      (node (ref "R35") (pin "1") (pinfunction "1_1") (pintype "passive"))
      (node (ref "R35_1") (pin "2") (pinfunction "2_2") (pintype "passive"))
    )
    (net (code "32") (name "/L1_2") (class "Default")
      (node (ref "R35") (pin "2") (pinfunction "2_2") (pintype "passive"))
      (node (ref "R36") (pin "1") (pinfunction "1_1") (pintype "passive"))
    )
    (net (code "33") (name "/L2") (class "Default")
      (node (ref "R48_1") (pin "1") (pinfunction "1_1") (pintype "passive"))
      (node (ref "U17") (pin "5") (pinfunction "IP-_5") (pintype "passive"))
      (node (ref "U17") (pin "6") (pinfunction "IP-_6") (pintype "passive"))
      (node (ref "U17") (pin "7") (pinfunction "IP-_7") (pintype "passive"))
      (node (ref "U17") (pin "8") (pinfunction "IP-_8") (pintype "passive"))
      (node (ref "X12") (pin "2") (pinfunction "2_2") (pintype "passive"))
    )
    (net (code "34") (name "/L2.1") (class "Default")
      (node (ref "K1") (pin "1") (pinfunction "1_1") (pintype "passive"))
      (node (ref "K2") (pin "1") (pinfunction "1_1") (pintype "passive"))
      (node (ref "U17") (pin "1") (pinfunction "IP+_1") (pintype "passive"))
      (node (ref "U17") (pin "2") (pinfunction "IP+_2") (pintype "passive"))
      (node (ref "U17") (pin "3") (pinfunction "IP+_3") (pintype "passive"))
      (node (ref "U17") (pin "4") (pinfunction "IP+_4") (pintype "passive"))
    )
    (net (code "35") (name "/L2_1") (class "Default")
      (node (ref "R48") (pin "2") (pinfunction "2_2") (pintype "passive"))
      (node (ref "R48_1") (pin "2") (pinfunction "2_2") (pintype "passive"))
    )
    (net (code "36") (name "/L2_2") (class "Default")
      (node (ref "R47") (pin "2") (pinfunction "2_2") (pintype "passive"))
      (node (ref "R48") (pin "1") (pinfunction "1_1") (pintype "passive"))
    )
    (net (code "37") (name "/L3") (class "Default")
      (node (ref "K1") (pin "8") (pinfunction "8_8") (pintype "passive"))
      (node (ref "X11") (pin "2") (pinfunction "2_2") (pintype "passive"))
    )
    (net (code "38") (name "/MAINS_PATH_STATE") (class "Default")
      (node (ref "C44") (pin "1") (pinfunction "1_1") (pintype "passive"))
      (node (ref "R51") (pin "2") (pinfunction "2_2") (pintype "passive"))
      (node (ref "R52") (pin "2") (pinfunction "2_2") (pintype "passive"))
      (node (ref "VD6") (pin "3") (pinfunction "3_3") (pintype "passive"))
    )
    (net (code "39") (name "/N1") (class "Default")
      (node (ref "K2") (pin "7") (pinfunction "7_7") (pintype "passive"))
      (node (ref "R40_1") (pin "1") (pinfunction "1_1") (pintype "passive"))
      (node (ref "X10") (pin "2") (pinfunction "2_2") (pintype "passive"))
    )
    (net (code "40") (name "/N1_1") (class "Default")
      (node (ref "R40") (pin "2") (pinfunction "2_2") (pintype "passive"))
      (node (ref "R40_1") (pin "2") (pinfunction "2_2") (pintype "passive"))
    )
    (net (code "41") (name "/N1_2") (class "Default")
      (node (ref "R39") (pin "2") (pinfunction "2_2") (pintype "passive"))
      (node (ref "R40") (pin "1") (pinfunction "1_1") (pintype "passive"))
    )
    (net (code "42") (name "/N1_3") (class "Default")
      (node (ref "R37") (pin "2") (pinfunction "2_2") (pintype "passive"))
      (node (ref "R39") (pin "1") (pinfunction "1_1") (pintype "passive"))
      (node (ref "U15") (pin "16") (pinfunction "VIMP_16") (pintype "passive"))
    )
    (net (code "43") (name "/N2") (class "Default")
      (node (ref "K1") (pin "2") (pinfunction "2_2") (pintype "passive"))
      (node (ref "K2") (pin "2") (pinfunction "2_2") (pintype "passive"))
      (node (ref "R44_1") (pin "1") (pinfunction "1_1") (pintype "passive"))
      (node (ref "X12") (pin "1") (pinfunction "1_1") (pintype "passive"))
    )
    (net (code "44") (name "/N2_1") (class "Default")
      (node (ref "R44") (pin "1") (pinfunction "1_1") (pintype "passive"))
      (node (ref "R44_1") (pin "2") (pinfunction "2_2") (pintype "passive"))
    )
    (net (code "45") (name "/N2_2") (class "Default")
      (node (ref "R44") (pin "2") (pinfunction "2_2") (pintype "passive"))
      (node (ref "R45") (pin "1") (pinfunction "1_1") (pintype "passive"))
    )
    (net (code "46") (name "/N2_3") (class "Default")
      (node (ref "R45") (pin "2") (pinfunction "2_2") (pintype "passive"))
      (node (ref "R46") (pin "1") (pinfunction "1_1") (pintype "passive"))
      (node (ref "U17") (pin "16") (pinfunction "VIMP_16") (pintype "passive"))
    )
    (net (code "47") (name "/N3") (class "Default")
      (node (ref "K1") (pin "7") (pinfunction "7_7") (pintype "passive"))
      (node (ref "X11") (pin "1") (pinfunction "1_1") (pintype "passive"))
    )
    (net (code "48") (name "/OUT1") (class "Default")
      (node (ref "Q1") (pin "1") (pinfunction "B_1") (pintype "passive"))
    )
    (net (code "49") (name "/OUT2") (class "Default")
      (node (ref "Q4") (pin "1") (pinfunction "B_1") (pintype "passive"))
    )
    (net (code "50") (name "/SPI0_CS") (class "Default")
      (node (ref "U33") (pin "5") (pinfunction "A3_5") (pintype "passive"))
    )
    (net (code "51") (name "/SPI0_MISO") (class "Default")
      (node (ref "U33") (pin "6") (pinfunction "A4_6") (pintype "passive"))
    )
    (net (code "52") (name "/SPI0_MOSI") (class "Default")
      (node (ref "U33") (pin "4") (pinfunction "A2_4") (pintype "passive"))
    )
    (net (code "53") (name "/SPI0_SCK") (class "Default")
      (node (ref "U33") (pin "3") (pinfunction "A1_3") (pintype "passive"))
    )
    (net (code "54") (name "/SPI1_CS") (class "Default")
      (node (ref "U30") (pin "5") (pinfunction "A3_5") (pintype "passive"))
    )
    (net (code "55") (name "/SPI1_MISO") (class "Default")
      (node (ref "U30") (pin "6") (pinfunction "A4_6") (pintype "passive"))
    )
    (net (code "56") (name "/SPI1_MOSI") (class "Default")
      (node (ref "U30") (pin "4") (pinfunction "A2_4") (pintype "passive"))
    )
    (net (code "57") (name "/SPI1_SCK") (class "Default")
      (node (ref "U30") (pin "3") (pinfunction "A1_3") (pintype "passive"))
    )
    (net (code "58") (name "/SW_INV_PATH") (class "Default")
      (node (ref "U16") (pin "1") (pinfunction "IN1_1") (pintype "power_in"))
    )
    (net (code "59") (name "/SW_MAINS_PATH") (class "Default")
      (node (ref "U16") (pin "2") (pinfunction "IN2_2") (pintype "power_in"))
    )
    (net (code "60") (name "ACC_DC_BUS") (class "Default")
      (node (ref "R110") (pin "1") (pinfunction "1_1") (pintype "passive"))
      (node (ref "R80") (pin "2") (pinfunction "2_2") (pintype "passive"))
    )
    (net (code "61") (name "AGND") (class "Default")
      (node (ref "C102") (pin "2") (pinfunction "2_2") (pintype "passive"))
      (node (ref "C103") (pin "2") (pinfunction "2_2") (pintype "passive"))
      (node (ref "C24") (pin "1") (pinfunction "1_1") (pintype "passive"))
      (node (ref "C25") (pin "1") (pinfunction "1_1") (pintype "passive"))
      (node (ref "C26") (pin "2") (pinfunction "2_2") (pintype "passive"))
      (node (ref "C77") (pin "2") (pinfunction "2_2") (pintype "passive"))
      (node (ref "C90") (pin "1") (pinfunction "1_1") (pintype "passive"))
      (node (ref "R112") (pin "1") (pinfunction "1_1") (pintype "passive"))
      (node (ref "R20") (pin "1") (pinfunction "1_1") (pintype "passive"))
      (node (ref "U13") (pin "4") (pinfunction "GND_4") (pintype "passive"))
      (node (ref "U22") (pin "4") (pinfunction "GND_4") (pintype "passive"))
      (node (ref "U27") (pin "2") (pinfunction "GND_2") (pintype "power_in"))
    )
    (net (code "62") (name "GND") (class "Default")
      (node (ref "C111") (pin "1") (pinfunction "1_1") (pintype "passive"))
      (node (ref "C112") (pin "1") (pinfunction "1_1") (pintype "passive"))
      (node (ref "C44") (pin "2") (pinfunction "2_2") (pintype "passive"))
      (node (ref "C49") (pin "2") (pinfunction "2_2") (pintype "passive"))
      (node (ref "Q1") (pin "2") (pinfunction "E_2") (pintype "passive"))
      (node (ref "Q4") (pin "2") (pinfunction "E_2") (pintype "passive"))
      (node (ref "R52") (pin "1") (pinfunction "1_1") (pintype "passive"))
      (node (ref "R54") (pin "1") (pinfunction "1_1") (pintype "passive"))
      (node (ref "U16") (pin "8") (pinfunction "GND_8") (pintype "power_in"))
      (node (ref "U29") (pin "1") (pinfunction "-Vin_1") (pintype "passive"))
      (node (ref "U30") (pin "2") (pinfunction "GND1_2") (pintype "passive"))
      (node (ref "U30") (pin "8") (pinfunction "GND1_8") (pintype "passive"))
      (node (ref "U31") (pin "1") (pinfunction "-Vin_1") (pintype "passive"))
      (node (ref "U33") (pin "2") (pinfunction "GND1_2") (pintype "passive"))
      (node (ref "U33") (pin "8") (pinfunction "GND1_8") (pintype "passive"))
      (node (ref "VD6") (pin "1") (pinfunction "1_1") (pintype "passive"))
      (node (ref "VD7") (pin "1") (pinfunction "1_1") (pintype "passive"))
    )
    (net (code "63") (name "I1+3V3") (class "Default")
      (node (ref "C106") (pin "1") (pinfunction "1_1") (pintype "passive"))
      (node (ref "C107") (pin "2") (pinfunction "2_2") (pintype "passive"))
      (node (ref "C50") (pin "1") (pinfunction "1_1") (pintype "passive"))
      (node (ref "U17") (pin "13") (pinfunction "VCC_13") (pintype "passive"))
      (node (ref "U28") (pin "5") (pinfunction "OUT_5") (pintype "power_in"))
      (node (ref "U30") (pin "16") (pinfunction "VDD2_16") (pintype "passive"))
    )
    (net (code "64") (name "I1_GND") (class "Default")
      (node (ref "C105") (pin "2") (pinfunction "2_2") (pintype "passive"))
      (node (ref "C106") (pin "2") (pinfunction "2_2") (pintype "passive"))
      (node (ref "C107") (pin "1") (pinfunction "1_1") (pintype "passive"))
      (node (ref "C50") (pin "2") (pinfunction "2_2") (pintype "passive"))
      (node (ref "R46") (pin "2") (pinfunction "2_2") (pintype "passive"))
      (node (ref "R47") (pin "1") (pinfunction "1_1") (pintype "passive"))
      (node (ref "U17") (pin "14") (pinfunction "GND_14") (pintype "passive"))
      (node (ref "U17") (pin "15") (pinfunction "VINN_15") (pintype "passive"))
      (node (ref "U28") (pin "2") (pinfunction "GND_2") (pintype "power_in"))
      (node (ref "U29") (pin "3") (pinfunction "-Vout_3") (pintype "passive"))
      (node (ref "U30") (pin "15") (pinfunction "GND2_15") (pintype "passive"))
      (node (ref "U30") (pin "9") (pinfunction "GND2_9") (pintype "passive"))
    )
    (net (code "65") (name "I2+3V3") (class "Default")
      (node (ref "C109") (pin "1") (pinfunction "1_1") (pintype "passive"))
      (node (ref "C110") (pin "2") (pinfunction "2_2") (pintype "passive"))
      (node (ref "C38") (pin "1") (pinfunction "1_1") (pintype "passive"))
      (node (ref "U15") (pin "13") (pinfunction "VCC_13") (pintype "passive"))
      (node (ref "U32") (pin "5") (pinfunction "OUT_5") (pintype "power_in"))
      (node (ref "U33") (pin "16") (pinfunction "VDD2_16") (pintype "passive"))
    )
    (net (code "66") (name "I2_GND") (class "Default")
      (node (ref "C108") (pin "2") (pinfunction "2_2") (pintype "passive"))
      (node (ref "C109") (pin "2") (pinfunction "2_2") (pintype "passive"))
      (node (ref "C110") (pin "1") (pinfunction "1_1") (pintype "passive"))
      (node (ref "C38") (pin "2") (pinfunction "2_2") (pintype "passive"))
      (node (ref "R36") (pin "2") (pinfunction "2_2") (pintype "passive"))
      (node (ref "R37") (pin "1") (pinfunction "1_1") (pintype "passive"))
      (node (ref "U15") (pin "14") (pinfunction "GND_14") (pintype "passive"))
      (node (ref "U15") (pin "15") (pinfunction "VINN_15") (pintype "passive"))
      (node (ref "U31") (pin "3") (pinfunction "-Vout_3") (pintype "passive"))
      (node (ref "U32") (pin "2") (pinfunction "GND_2") (pintype "power_in"))
      (node (ref "U33") (pin "15") (pinfunction "GND2_15") (pintype "passive"))
      (node (ref "U33") (pin "9") (pinfunction "GND2_9") (pintype "passive"))
    )
    (net (code "67") (name "Net-(C32-Pad1)") (class "Default")
      (node (ref "C32") (pin "1") (pinfunction "1_1") (pintype "passive"))
      (node (ref "R30") (pin "2") (pinfunction "2_2") (pintype "passive"))
    )
    (net (code "68") (name "Net-(LED1-Pad2)") (class "Default")
      (node (ref "LED1") (pin "2") (pinfunction "2_2") (pintype "passive"))
      (node (ref "R19") (pin "2") (pinfunction "2_2") (pintype "passive"))
    )
    (net (code "69") (name "Net-(LED2-Pad2)") (class "Default")
      (node (ref "LED2") (pin "2") (pinfunction "2_2") (pintype "passive"))
      (node (ref "R26") (pin "2") (pinfunction "2_2") (pintype "passive"))
    )
    (net (code "70") (name "Net-(OPT1-Pad1)") (class "Default")
      (node (ref "OPT1") (pin "1") (pinfunction "1_1") (pintype "passive"))
      (node (ref "R18") (pin "2") (pinfunction "2_2") (pintype "passive"))
    )
    (net (code "71") (name "Net-(OPT1-Pad4)") (class "Default")
      (node (ref "OPT1") (pin "4") (pinfunction "4_4") (pintype "passive"))
      (node (ref "X7") (pin "1") (pinfunction "1_1") (pintype "passive"))
    )
    (net (code "72") (name "Net-(OPT1-Pad6)") (class "Default")
      (node (ref "OPT1") (pin "6") (pinfunction "6_6") (pintype "passive"))
      (node (ref "X7") (pin "2") (pinfunction "2_2") (pintype "passive"))
    )
    (net (code "73") (name "Net-(OPT2-Pad1)") (class "Default")
      (node (ref "OPT2") (pin "1") (pinfunction "1_1") (pintype "passive"))
      (node (ref "R25") (pin "2") (pinfunction "2_2") (pintype "passive"))
    )
    (net (code "74") (name "Net-(OPT2-Pad4)") (class "Default")
      (node (ref "OPT2") (pin "4") (pinfunction "4_4") (pintype "passive"))
      (node (ref "X9") (pin "1") (pinfunction "1_1") (pintype "passive"))
    )
    (net (code "75") (name "Net-(OPT2-Pad6)") (class "Default")
      (node (ref "OPT2") (pin "6") (pinfunction "6_6") (pintype "passive"))
      (node (ref "X9") (pin "2") (pinfunction "2_2") (pintype "passive"))
    )
    (net (code "76") (name "Net-(Q1-C)") (class "Default")
      (node (ref "OPT1") (pin "2") (pinfunction "2_2") (pintype "passive"))
      (node (ref "Q1") (pin "3") (pinfunction "C_3") (pintype "passive"))
      (node (ref "R19") (pin "1") (pinfunction "1_1") (pintype "passive"))
    )
    (net (code "77") (name "Net-(Q2-S)") (class "Default")
      (node (ref "Q2") (pin "2") (pinfunction "S_2") (pintype "passive"))
      (node (ref "Q3") (pin "2") (pinfunction "S_2") (pintype "passive"))
    )
    (net (code "78") (name "Net-(Q3-D)") (class "Default")
      (node (ref "B1") (pin "1") (pinfunction "1_1") (pintype "passive"))
      (node (ref "Q3") (pin "3") (pinfunction "D_3") (pintype "passive"))
      (node (ref "R24") (pin "2") (pinfunction "2_2") (pintype "passive"))
      (node (ref "U14") (pin "9") (pinfunction "SENSE_9") (pintype "passive"))
    )
    (net (code "79") (name "Net-(Q4-C)") (class "Default")
      (node (ref "OPT2") (pin "2") (pinfunction "2_2") (pintype "passive"))
      (node (ref "Q4") (pin "3") (pinfunction "C_3") (pintype "passive"))
      (node (ref "R26") (pin "1") (pinfunction "1_1") (pintype "passive"))
    )
    (net (code "80") (name "Net-(U13-OUT)") (class "Default")
      (node (ref "R21") (pin "1") (pinfunction "1_1") (pintype "passive"))
      (node (ref "U13") (pin "8") (pinfunction "OUT_8") (pintype "passive"))
    )
    (net (code "81") (name "Net-(U14-OV)") (class "Default")
      (node (ref "R29") (pin "1") (pinfunction "1_1") (pintype "passive"))
      (node (ref "R33") (pin "2") (pinfunction "2_2") (pintype "passive"))
      (node (ref "U14") (pin "3") (pinfunction "OV_3") (pintype "passive"))
    )
    (net (code "82") (name "Net-(U14-RETRY)") (class "Default")
      (node (ref "C29") (pin "1") (pinfunction "1_1") (pintype "passive"))
      (node (ref "U14") (pin "4") (pinfunction "RETRY_4") (pintype "passive"))
    )
    (net (code "83") (name "Net-(U16-OUT1)") (class "Default")
      (node (ref "K1") (pin "3") (pinfunction "3_3") (pintype "passive"))
      (node (ref "U16") (pin "16") (pinfunction "OUT1_16") (pintype "power_in"))
    )
    (net (code "84") (name "Net-(U16-OUT2)") (class "Default")
      (node (ref "K2") (pin "3") (pinfunction "3_3") (pintype "passive"))
      (node (ref "U16") (pin "15") (pinfunction "OUT2_15") (pintype "power_in"))
    )
    (net (code "85") (name "Net-(U22-OUT)") (class "Default")
      (node (ref "R103") (pin "1") (pinfunction "1_1") (pintype "passive"))
      (node (ref "U22") (pin "8") (pinfunction "OUT_8") (pintype "passive"))
    )
    (net (code "86") (name "Net-(U27-IN+)") (class "Default")
      (node (ref "C102") (pin "1") (pinfunction "1_1") (pintype "passive"))
      (node (ref "R110") (pin "2") (pinfunction "2_2") (pintype "passive"))
      (node (ref "R112") (pin "2") (pinfunction "2_2") (pintype "passive"))
      (node (ref "U27") (pin "3") (pinfunction "IN+_3") (pintype "passive"))
    )
    (net (code "87") (name "Net-(U27-IN-)") (class "Default")
      (node (ref "C101") (pin "2") (pinfunction "2_2") (pintype "passive"))
      (node (ref "R109") (pin "2") (pinfunction "2_2") (pintype "passive"))
      (node (ref "R111") (pin "1") (pinfunction "1_1") (pintype "passive"))
      (node (ref "U27") (pin "4") (pinfunction "IN-_4") (pintype "passive"))
    )
    (net (code "88") (name "Net-(VD4-C)") (class "Default")
      (node (ref "K1") (pin "5") (pinfunction "5_5") (pintype "passive"))
      (node (ref "K2") (pin "6") (pinfunction "6_6") (pintype "passive"))
      (node (ref "R51") (pin "1") (pinfunction "1_1") (pintype "passive"))
      (node (ref "VD4") (pin "1") (pinfunction "C_1") (pintype "passive"))
    )
    (net (code "89") (name "Net-(VD5-C)") (class "Default")
      (node (ref "K1") (pin "6") (pinfunction "6_6") (pintype "passive"))
      (node (ref "K2") (pin "5") (pinfunction "5_5") (pintype "passive"))
      (node (ref "R53") (pin "1") (pinfunction "1_1") (pintype "passive"))
      (node (ref "VD5") (pin "1") (pinfunction "C_1") (pintype "passive"))
    )
    (net (code "90") (name "PGND") (class "Default")
      (node (ref "C27") (pin "2") (pinfunction "2_2") (pintype "passive"))
      (node (ref "C28") (pin "2") (pinfunction "2_2") (pintype "passive"))
      (node (ref "C29") (pin "2") (pinfunction "2_2") (pintype "passive"))
      (node (ref "C32") (pin "2") (pinfunction "2_2") (pintype "passive"))
      (node (ref "R109") (pin "1") (pinfunction "1_1") (pintype "passive"))
      (node (ref "R31") (pin "1") (pinfunction "1_1") (pintype "passive"))
      (node (ref "R32") (pin "1") (pinfunction "1_1") (pintype "passive"))
      (node (ref "R33") (pin "1") (pinfunction "1_1") (pintype "passive"))
      (node (ref "U14") (pin "5") (pinfunction "GND_5") (pintype "passive"))
      (node (ref "VD3") (pin "1") (pinfunction "C_1") (pintype "passive"))
      (node (ref "X6") (pin "2") (pinfunction "2_2") (pintype "passive"))
      (node (ref "X8") (pin "1") (pinfunction "1_1") (pintype "passive"))
    )
    (net (code "91") (name "PWR24F") (class "Default")
      (node (ref "K1") (pin "4") (pinfunction "4_4") (pintype "passive"))
      (node (ref "K2") (pin "4") (pinfunction "4_4") (pintype "passive"))
      (node (ref "U16") (pin "9") (pinfunction "COMD_9") (pintype "power_in"))
      (node (ref "VD4") (pin "2") (pinfunction "A_2") (pintype "passive"))
      (node (ref "VD5") (pin "2") (pinfunction "A_2") (pintype "passive"))
    )
    (net (code "92") (name "VREF_1.65V") (class "Default")
      (node (ref "U13") (pin "6") (pinfunction "REF2_6") (pintype "passive"))
      (node (ref "U13") (pin "7") (pinfunction "REF1_7") (pintype "passive"))
      (node (ref "U22") (pin "6") (pinfunction "REF2_6") (pintype "passive"))
      (node (ref "U22") (pin "7") (pinfunction "REF1_7") (pintype "passive"))
    )
    (net (code "93") (name "unconnected-(OPT1-Pad5)") (class "Default")
      (node (ref "OPT1") (pin "5") (pinfunction "5_5") (pintype "passive"))
    )
    (net (code "94") (name "unconnected-(OPT2-Pad5)") (class "Default")
      (node (ref "OPT2") (pin "5") (pinfunction "5_5") (pintype "passive"))
    )
    (net (code "95") (name "unconnected-(U13-NC-Pad1)") (class "Default")
      (node (ref "U13") (pin "1") (pinfunction "NC_1") (pintype "passive"))
    )
    (net (code "96") (name "unconnected-(U16-IN3-Pad3)") (class "Default")
      (node (ref "U16") (pin "3") (pinfunction "IN3_3") (pintype "power_in"))
    )
    (net (code "97") (name "unconnected-(U16-IN4-Pad4)") (class "Default")
      (node (ref "U16") (pin "4") (pinfunction "IN4_4") (pintype "power_in"))
    )
    (net (code "98") (name "unconnected-(U16-IN5-Pad5)") (class "Default")
      (node (ref "U16") (pin "5") (pinfunction "IN5_5") (pintype "power_in"))
    )
    (net (code "99") (name "unconnected-(U16-IN6-Pad6)") (class "Default")
      (node (ref "U16") (pin "6") (pinfunction "IN6_6") (pintype "power_in"))
    )
    (net (code "100") (name "unconnected-(U16-IN7-Pad7)") (class "Default")
      (node (ref "U16") (pin "7") (pinfunction "IN7_7") (pintype "power_in"))
    )
    (net (code "101") (name "unconnected-(U16-OUT3-Pad14)") (class "Default")
      (node (ref "U16") (pin "14") (pinfunction "OUT3_14") (pintype "power_in"))
    )
    (net (code "102") (name "unconnected-(U16-OUT4-Pad13)") (class "Default")
      (node (ref "U16") (pin "13") (pinfunction "OUT4_13") (pintype "power_in"))
    )
    (net (code "103") (name "unconnected-(U16-OUT5-Pad12)") (class "Default")
      (node (ref "U16") (pin "12") (pinfunction "OUT5_12") (pintype "power_in"))
    )
    (net (code "104") (name "unconnected-(U16-OUT6-Pad11)") (class "Default")
      (node (ref "U16") (pin "11") (pinfunction "OUT6_11") (pintype "power_in"))
    )
    (net (code "105") (name "unconnected-(U16-OUT7-Pad10)") (class "Default")
      (node (ref "U16") (pin "10") (pinfunction "OUT7_10") (pintype "power_in"))
    )
    (net (code "106") (name "unconnected-(U22-NC-Pad1)") (class "Default")
      (node (ref "U22") (pin "1") (pinfunction "NC_1") (pintype "passive"))
    )
    (net (code "107") (name "unconnected-(U30-EN2-Pad10)") (class "Default")
      (node (ref "U30") (pin "10") (pinfunction "EN2_10") (pintype "passive"))
    )
    (net (code "108") (name "unconnected-(U30-NC-Pad7)") (class "Default")
      (node (ref "U30") (pin "7") (pinfunction "NC_7") (pintype "passive"))
    )
    (net (code "109") (name "unconnected-(U33-EN2-Pad10)") (class "Default")
      (node (ref "U33") (pin "10") (pinfunction "EN2_10") (pintype "passive"))
    )
    (net (code "110") (name "unconnected-(U33-NC-Pad7)") (class "Default")
      (node (ref "U33") (pin "7") (pinfunction "NC_7") (pintype "passive"))
    )
  )
)
